# PCB_moved_parts_3.net
KiCad netlist of a schematic drawn in EAGLE
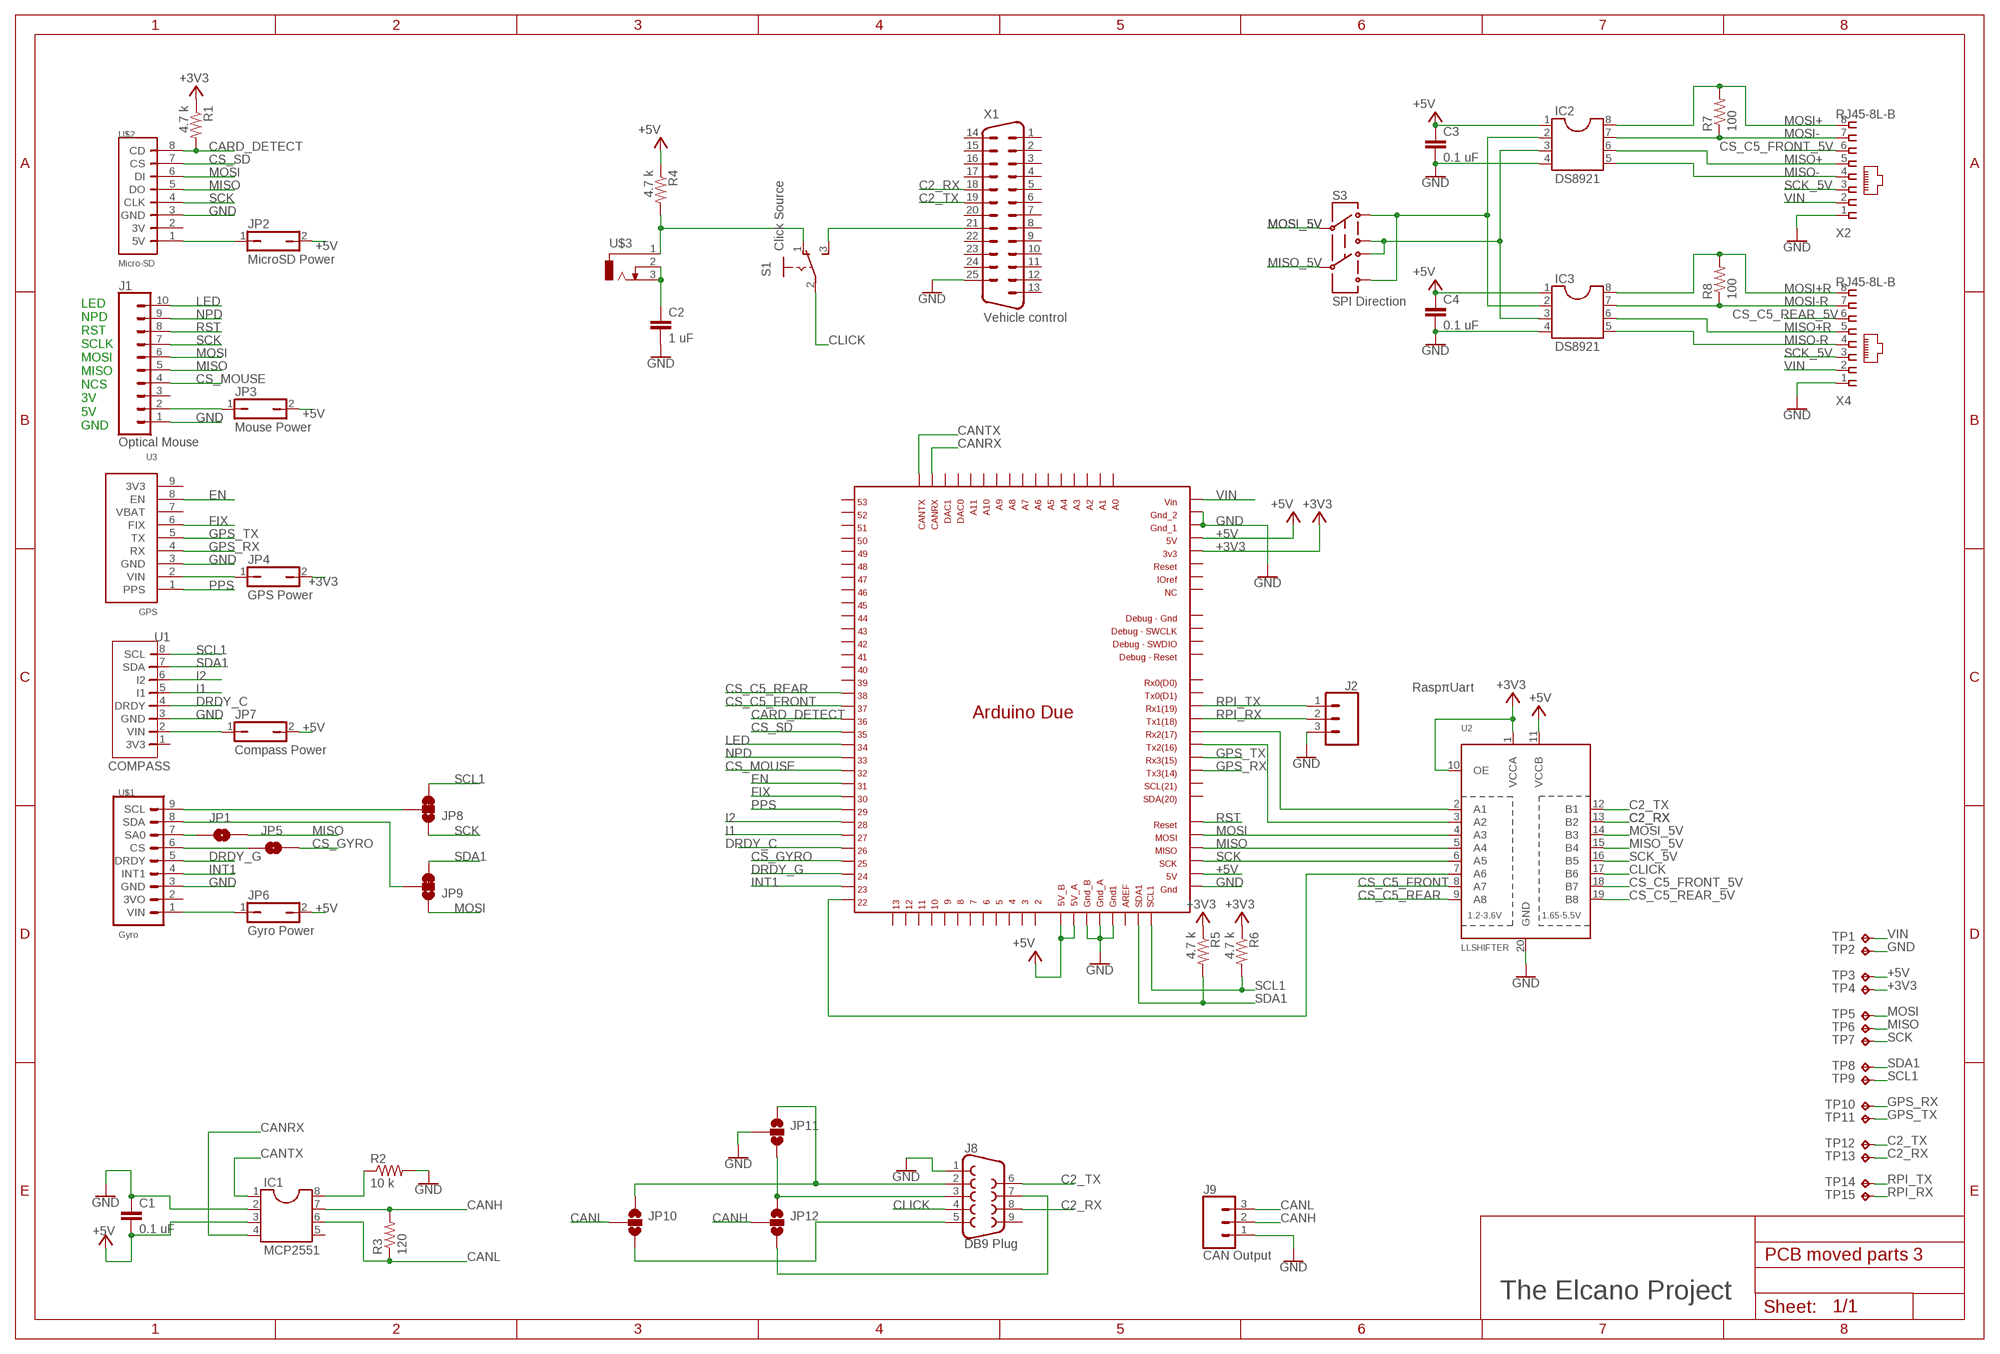
[diagram p0: schematic, sheet 1]

(export (version "E")
  (design (tool "Eeschema 10.0.6"))
  (components
    (comp (ref "C1")
      (value "0.1 uF")
      (footprint "eagle-import:C2.5-5")
      (libsource (lib "eagle-import") (part "C2.5/5"))
    )
    (comp (ref "C2")
      (value "1 uF")
      (footprint "eagle-import:C2.5-5")
      (libsource (lib "eagle-import") (part "C2.5/5"))
    )
    (comp (ref "C3")
      (value "0.1 uF")
      (footprint "eagle-import:C2.5-5")
      (libsource (lib "eagle-import") (part "C2.5/5"))
    )
    (comp (ref "C4")
      (value "0.1 uF")
      (footprint "eagle-import:C2.5-5")
      (libsource (lib "eagle-import") (part "C2.5/5"))
    )
    (comp (ref "IC1")
      (value "MCP2551")
      (footprint "eagle-import:DIL08")
      (libsource (lib "eagle-import") (part "DIL8"))
    )
    (comp (ref "IC2")
      (value "DS8921")
      (footprint "eagle-import:DIL08")
      (libsource (lib "eagle-import") (part "DIL8"))
    )
    (comp (ref "IC3")
      (value "DS8921")
      (footprint "eagle-import:DIL08")
      (libsource (lib "eagle-import") (part "DIL8"))
    )
    (comp (ref "J1")
      (value "Optical Mouse")
      (footprint "eagle-import:1X10")
      (libsource (lib "eagle-import") (part "CONN_10{dblquote}"))
    )
    (comp (ref "J2")
      (value "RaspπUart")
      (footprint "eagle-import:1X03")
      (libsource (lib "eagle-import") (part "CONN_02"))
    )
    (comp (ref "J8")
      (value "DB9 Plug")
      (footprint "eagle-import:DB9_MALE")
      (fields (field (name "SPICEPREFIX") "X"))
      (libsource (lib "eagle-import") (part "DB9MALE"))
    )
    (comp (ref "J9")
      (value "CAN Output")
      (footprint "eagle-import:SCREWTERMINAL-5MM-3")
      (libsource (lib "eagle-import") (part "CONN_03-SCREW-5MM"))
    )
    (comp (ref "JP1")
      (value "JUMPER-SMT_2_NO_SILK")
      (footprint "eagle-import:SMT-JUMPER_2_NO_SILK")
      (libsource (lib "eagle-import") (part "JUMPER-SMT_2_NO_SILK"))
    )
    (comp (ref "JP2")
      (value "MicroSD Power")
      (footprint "eagle-import:JP1")
      (libsource (lib "eagle-import") (part "JP1Q"))
    )
    (comp (ref "JP3")
      (value "Mouse Power")
      (footprint "eagle-import:JP1")
      (libsource (lib "eagle-import") (part "JP1Q"))
    )
    (comp (ref "JP4")
      (value "GPS Power")
      (footprint "eagle-import:JP1")
      (libsource (lib "eagle-import") (part "JP1Q"))
    )
    (comp (ref "JP5")
      (value "JUMPER-SMT_2_NO_SILK")
      (footprint "eagle-import:SMT-JUMPER_2_NO_SILK")
      (libsource (lib "eagle-import") (part "JUMPER-SMT_2_NO_SILK"))
    )
    (comp (ref "JP6")
      (value "Gyro Power")
      (footprint "eagle-import:JP1")
      (libsource (lib "eagle-import") (part "JP1Q"))
    )
    (comp (ref "JP7")
      (value "Compass Power")
      (footprint "eagle-import:JP1")
      (libsource (lib "eagle-import") (part "JP1Q"))
    )
    (comp (ref "JP8")
      (value "JUMPER-SMT_3_1-NC_TRACE_SILK")
      (footprint "eagle-import:SMT-JUMPER_3_1-NC_TRACE_SILK")
      (libsource (lib "eagle-import") (part "JUMPER-SMT_3_1-NC_TRACE_SILK"))
    )
    (comp (ref "JP9")
      (value "JUMPER-SMT_3_1-NC_TRACE_SILK")
      (footprint "eagle-import:SMT-JUMPER_3_1-NC_TRACE_SILK")
      (libsource (lib "eagle-import") (part "JUMPER-SMT_3_1-NC_TRACE_SILK"))
    )
    (comp (ref "JP10")
      (value "JUMPER-SMT_3_NO_SILK")
      (footprint "eagle-import:SMT-JUMPER_3_NO_SILK")
      (libsource (lib "eagle-import") (part "JUMPER-SMT_3_NO_SILK"))
    )
    (comp (ref "JP11")
      (value "JUMPER-SMT_3_NO_SILK")
      (footprint "eagle-import:SMT-JUMPER_3_NO_SILK")
      (libsource (lib "eagle-import") (part "JUMPER-SMT_3_NO_SILK"))
    )
    (comp (ref "JP12")
      (value "JUMPER-SMT_3_NO_SILK")
      (footprint "eagle-import:SMT-JUMPER_3_NO_SILK")
      (libsource (lib "eagle-import") (part "JUMPER-SMT_3_NO_SILK"))
    )
    (comp (ref "MCU2")
      (value "DUE(NORMAL)")
      (footprint "eagle-import:DUE(NORMAL)")
      (libsource (lib "eagle-import") (part "DUE(NORMAL)"))
    )
    (comp (ref "R1")
      (value "4.7 k")
      (footprint "eagle-import:0204_7")
      (libsource (lib "eagle-import") (part "resistor_348_R-US_0204/7"))
    )
    (comp (ref "R2")
      (value "10 k")
      (footprint "eagle-import:0204_7")
      (libsource (lib "eagle-import") (part "R-US_0204/7"))
    )
    (comp (ref "R3")
      (value "120")
      (footprint "eagle-import:0204_7")
      (libsource (lib "eagle-import") (part "R-US_0204/7"))
    )
    (comp (ref "R4")
      (value "4.7 k")
      (footprint "eagle-import:0204_7")
      (libsource (lib "eagle-import") (part "resistor_348_R-US_0204/7"))
    )
    (comp (ref "R5")
      (value "4.7 k")
      (footprint "eagle-import:0204_7")
      (libsource (lib "eagle-import") (part "resistor_348_R-US_0204/7"))
    )
    (comp (ref "R6")
      (value "4.7 k")
      (footprint "eagle-import:0204_7")
      (libsource (lib "eagle-import") (part "resistor_348_R-US_0204/7"))
    )
    (comp (ref "R7")
      (value "100")
      (footprint "eagle-import:0204_7")
      (libsource (lib "eagle-import") (part "R-US_0204/7"))
    )
    (comp (ref "R8")
      (value "100")
      (footprint "eagle-import:0204_7")
      (libsource (lib "eagle-import") (part "R-US_0204/7"))
    )
    (comp (ref "S1")
      (value "Click Source")
      (footprint "eagle-import:255SB")
      (libsource (lib "eagle-import") (part "255SB"))
    )
    (comp (ref "S3")
      (value "SPI Direction")
      (footprint "eagle-import:DPDT")
      (libsource (lib "eagle-import") (part "DPDT"))
    )
    (comp (ref "TP1")
      (value "TPPAD1-17")
      (footprint "eagle-import:P1-17")
      (libsource (lib "eagle-import") (part "TPPAD1-17"))
    )
    (comp (ref "TP2")
      (value "TPPAD1-17")
      (footprint "eagle-import:P1-17")
      (libsource (lib "eagle-import") (part "TPPAD1-17"))
    )
    (comp (ref "TP3")
      (value "TPPAD1-17")
      (footprint "eagle-import:P1-17")
      (libsource (lib "eagle-import") (part "TPPAD1-17"))
    )
    (comp (ref "TP4")
      (value "TPPAD1-17")
      (footprint "eagle-import:P1-17")
      (libsource (lib "eagle-import") (part "TPPAD1-17"))
    )
    (comp (ref "TP5")
      (value "TPPAD1-17")
      (footprint "eagle-import:P1-17")
      (libsource (lib "eagle-import") (part "TPPAD1-17"))
    )
    (comp (ref "TP6")
      (value "TPPAD1-17")
      (footprint "eagle-import:P1-17")
      (libsource (lib "eagle-import") (part "TPPAD1-17"))
    )
    (comp (ref "TP7")
      (value "TPPAD1-17")
      (footprint "eagle-import:P1-17")
      (libsource (lib "eagle-import") (part "TPPAD1-17"))
    )
    (comp (ref "TP8")
      (value "TPPAD1-17")
      (footprint "eagle-import:P1-17")
      (libsource (lib "eagle-import") (part "TPPAD1-17"))
    )
    (comp (ref "TP9")
      (value "TPPAD1-17")
      (footprint "eagle-import:P1-17")
      (libsource (lib "eagle-import") (part "TPPAD1-17"))
    )
    (comp (ref "TP10")
      (value "TPPAD1-17")
      (footprint "eagle-import:P1-17")
      (libsource (lib "eagle-import") (part "TPPAD1-17"))
    )
    (comp (ref "TP11")
      (value "TPPAD1-17")
      (footprint "eagle-import:P1-17")
      (libsource (lib "eagle-import") (part "TPPAD1-17"))
    )
    (comp (ref "TP12")
      (value "TPPAD1-17")
      (footprint "eagle-import:P1-17")
      (libsource (lib "eagle-import") (part "TPPAD1-17"))
    )
    (comp (ref "TP13")
      (value "TPPAD1-17")
      (footprint "eagle-import:P1-17")
      (libsource (lib "eagle-import") (part "TPPAD1-17"))
    )
    (comp (ref "TP14")
      (value "TPPAD1-17")
      (footprint "eagle-import:P1-17")
      (libsource (lib "eagle-import") (part "TPPAD1-17"))
    )
    (comp (ref "TP15")
      (value "TPPAD1-17")
      (footprint "eagle-import:P1-17")
      (libsource (lib "eagle-import") (part "TPPAD1-17"))
    )
    (comp (ref "U$1")
      (value "Gyro")
      (footprint "eagle-import:ELGYRO")
      (libsource (lib "eagle-import") (part "ELGYRO_L3GD20H"))
    )
    (comp (ref "U$2")
      (value "Micro-SD")
      (footprint "eagle-import:ELSDCARD")
      (libsource (lib "eagle-import") (part "MINI_SD"))
    )
    (comp (ref "U$3")
      (value "2.5MMJACK")
      (footprint "eagle-import:2.5MMJACK")
      (libsource (lib "eagle-import") (part "2.5MMJACK"))
    )
    (comp (ref "U1")
      (value "COMPASS")
      (footprint "eagle-import:ELCOMPASS")
      (libsource (lib "eagle-import") (part "ELCOMPASS"))
    )
    (comp (ref "U2")
      (value "LLSHIFTER")
      (footprint "eagle-import:ELSHIFTER")
      (libsource (lib "eagle-import") (part "ELSHIFTER"))
    )
    (comp (ref "U3")
      (value "GPS")
      (footprint "eagle-import:ELGPS")
      (libsource (lib "eagle-import") (part "ELGPS"))
    )
    (comp (ref "X1")
      (value "Vehicle control")
      (footprint "eagle-import:M25H")
      (libsource (lib "eagle-import") (part "M25H"))
    )
    (comp (ref "X2")
      (value "RJ45-8L-B")
      (footprint "eagle-import:RJ45-NO-SHIELD")
      (fields (field (name "MF") "TYCO ELECTRONICS"))
      (libsource (lib "eagle-import") (part "RJ45-8L-B"))
    )
    (comp (ref "X4")
      (value "RJ45-8L-B")
      (footprint "eagle-import:RJ45-NO-SHIELD")
      (fields (field (name "MF") "TYCO ELECTRONICS"))
      (libsource (lib "eagle-import") (part "RJ45-8L-B"))
    )
  )
  (nets
    (net (code "1") (name "+3V3") (class "Default")
      (node (ref "JP4") (pin "2") (pinfunction "2_2") (pintype "passive"))
      (node (ref "MCU2") (pin "3V3") (pinfunction "3V3_3V3") (pintype "bidirectional"))
      (node (ref "R1") (pin "1") (pinfunction "1_1") (pintype "passive"))
      (node (ref "R5") (pin "1") (pinfunction "1_1") (pintype "passive"))
      (node (ref "R6") (pin "1") (pinfunction "1_1") (pintype "passive"))
      (node (ref "TP4") (pin "TP") (pinfunction "TP_TP") (pintype "input"))
      (node (ref "U2") (pin "1") (pinfunction "VCCA_1") (pintype "power_in"))
      (node (ref "U2") (pin "10") (pinfunction "OE_10") (pintype "bidirectional"))
    )
    (net (code "2") (name "+5V") (class "Default")
      (node (ref "C1") (pin "2") (pinfunction "2_2") (pintype "passive"))
      (node (ref "C3") (pin "1") (pinfunction "1_1") (pintype "passive"))
      (node (ref "C4") (pin "1") (pinfunction "1_1") (pintype "passive"))
      (node (ref "IC1") (pin "3") (pinfunction "3_3") (pintype "passive"))
      (node (ref "IC2") (pin "1") (pinfunction "1_1") (pintype "passive"))
      (node (ref "IC3") (pin "1") (pinfunction "1_1") (pintype "passive"))
      (node (ref "JP2") (pin "2") (pinfunction "2_2") (pintype "passive"))
      (node (ref "JP3") (pin "2") (pinfunction "2_2") (pintype "passive"))
      (node (ref "JP6") (pin "2") (pinfunction "2_2") (pintype "passive"))
      (node (ref "JP7") (pin "2") (pinfunction "2_2") (pintype "passive"))
      (node (ref "MCU2") (pin "5V") (pinfunction "5V_5V") (pintype "bidirectional"))
      (node (ref "MCU2") (pin "5V_A") (pinfunction "5V_A_5V_A") (pintype "bidirectional"))
      (node (ref "MCU2") (pin "5V_B") (pinfunction "5V_B_5V_B") (pintype "bidirectional"))
      (node (ref "MCU2") (pin "GND_ICSP") (pinfunction "GND_ICSP_GND_ICSP") (pintype "bidirectional"))
      (node (ref "R4") (pin "1") (pinfunction "1_1") (pintype "passive"))
      (node (ref "TP3") (pin "TP") (pinfunction "TP_TP") (pintype "input"))
      (node (ref "U2") (pin "11") (pinfunction "VCCB_11") (pintype "power_in"))
    )
    (net (code "3") (name "/C2_RX") (class "Default")
      (node (ref "J8") (pin "8") (pinfunction "8_8") (pintype "passive"))
      (node (ref "TP13") (pin "TP") (pinfunction "TP_TP") (pintype "input"))
      (node (ref "U2") (pin "13") (pinfunction "B2_13") (pintype "bidirectional"))
      (node (ref "X1") (pin "18") (pinfunction "18_18") (pintype "passive"))
    )
    (net (code "4") (name "/C2_TX") (class "Default")
      (node (ref "J8") (pin "6") (pinfunction "6_6") (pintype "passive"))
      (node (ref "TP12") (pin "TP") (pinfunction "TP_TP") (pintype "input"))
      (node (ref "U2") (pin "12") (pinfunction "B1_12") (pintype "bidirectional"))
      (node (ref "X1") (pin "19") (pinfunction "19_19") (pintype "passive"))
    )
    (net (code "5") (name "/CANH") (class "Default")
      (node (ref "IC1") (pin "7") (pinfunction "7_7") (pintype "passive"))
      (node (ref "J9") (pin "2") (pinfunction "2_2") (pintype "passive"))
      (node (ref "JP12") (pin "2") (pinfunction "2_2") (pintype "passive"))
      (node (ref "R3") (pin "2") (pinfunction "2_2") (pintype "passive"))
    )
    (net (code "6") (name "/CANL") (class "Default")
      (node (ref "IC1") (pin "6") (pinfunction "6_6") (pintype "passive"))
      (node (ref "J9") (pin "3") (pinfunction "3_3") (pintype "passive"))
      (node (ref "JP10") (pin "2") (pinfunction "2_2") (pintype "passive"))
      (node (ref "R3") (pin "1") (pinfunction "1_1") (pintype "passive"))
    )
    (net (code "7") (name "/CANRX") (class "Default")
      (node (ref "IC1") (pin "4") (pinfunction "4_4") (pintype "passive"))
      (node (ref "MCU2") (pin "CANRX") (pinfunction "CANRX_CANRX") (pintype "bidirectional"))
    )
    (net (code "8") (name "/CANTX") (class "Default")
      (node (ref "IC1") (pin "1") (pinfunction "1_1") (pintype "passive"))
      (node (ref "MCU2") (pin "CANTX") (pinfunction "CANTX_CANTX") (pintype "bidirectional"))
    )
    (net (code "9") (name "/CARD_DETECT") (class "Default")
      (node (ref "MCU2") (pin "36") (pinfunction "36_36") (pintype "bidirectional"))
      (node (ref "R1") (pin "2") (pinfunction "2_2") (pintype "passive"))
      (node (ref "U$2") (pin "8") (pinfunction "CD_8") (pintype "bidirectional"))
    )
    (net (code "10") (name "/CLICK") (class "Default")
      (node (ref "J8") (pin "4") (pinfunction "4_4") (pintype "passive"))
      (node (ref "S1") (pin "2") (pinfunction "P_2") (pintype "passive"))
      (node (ref "U2") (pin "17") (pinfunction "B6_17") (pintype "bidirectional"))
    )
    (net (code "11") (name "/CS_C5_FRONT") (class "Default")
      (node (ref "MCU2") (pin "37") (pinfunction "37_37") (pintype "bidirectional"))
      (node (ref "U2") (pin "8") (pinfunction "A7_8") (pintype "bidirectional"))
    )
    (net (code "12") (name "/CS_C5_FRONT_5V") (class "Default")
      (node (ref "U2") (pin "18") (pinfunction "B7_18") (pintype "bidirectional"))
      (node (ref "X2") (pin "6") (pinfunction "6_6") (pintype "passive"))
    )
    (net (code "13") (name "/CS_C5_REAR") (class "Default")
      (node (ref "MCU2") (pin "38") (pinfunction "38_38") (pintype "bidirectional"))
      (node (ref "U2") (pin "9") (pinfunction "A8_9") (pintype "bidirectional"))
    )
    (net (code "14") (name "/CS_C5_REAR_5V") (class "Default")
      (node (ref "U2") (pin "19") (pinfunction "B8_19") (pintype "bidirectional"))
      (node (ref "X4") (pin "6") (pinfunction "6_6") (pintype "passive"))
    )
    (net (code "15") (name "/CS_GYRO") (class "Default")
      (node (ref "JP5") (pin "2") (pinfunction "2_2") (pintype "passive"))
      (node (ref "MCU2") (pin "25") (pinfunction "25_25") (pintype "bidirectional"))
    )
    (net (code "16") (name "/CS_MOUSE") (class "Default")
      (node (ref "J1") (pin "4") (pinfunction "4_4") (pintype "passive"))
      (node (ref "MCU2") (pin "32") (pinfunction "32_32") (pintype "bidirectional"))
    )
    (net (code "17") (name "/CS_SD") (class "Default")
      (node (ref "MCU2") (pin "35") (pinfunction "35_35") (pintype "bidirectional"))
      (node (ref "U$2") (pin "7") (pinfunction "CS_7") (pintype "bidirectional"))
    )
    (net (code "18") (name "/DRDY_C") (class "Default")
      (node (ref "MCU2") (pin "26") (pinfunction "26_26") (pintype "bidirectional"))
      (node (ref "U1") (pin "4") (pinfunction "DRDY_4") (pintype "bidirectional"))
    )
    (net (code "19") (name "/DRDY_G") (class "Default")
      (node (ref "MCU2") (pin "24") (pinfunction "24_24") (pintype "bidirectional"))
      (node (ref "U$1") (pin "5") (pinfunction "DRDY_5") (pintype "passive"))
    )
    (net (code "20") (name "/EN") (class "Default")
      (node (ref "MCU2") (pin "31") (pinfunction "31_31") (pintype "bidirectional"))
      (node (ref "U3") (pin "8") (pinfunction "EN_8") (pintype "bidirectional"))
    )
    (net (code "21") (name "/FIX") (class "Default")
      (node (ref "MCU2") (pin "30") (pinfunction "30_30") (pintype "bidirectional"))
      (node (ref "U3") (pin "6") (pinfunction "FIX_6") (pintype "bidirectional"))
    )
    (net (code "22") (name "/GPS_RX") (class "Default")
      (node (ref "MCU2") (pin "TX3") (pinfunction "TX3_TX3") (pintype "bidirectional"))
      (node (ref "TP10") (pin "TP") (pinfunction "TP_TP") (pintype "input"))
      (node (ref "U3") (pin "4") (pinfunction "RX_4") (pintype "input"))
    )
    (net (code "23") (name "/GPS_TX") (class "Default")
      (node (ref "MCU2") (pin "RX3") (pinfunction "RX3_RX3") (pintype "bidirectional"))
      (node (ref "TP11") (pin "TP") (pinfunction "TP_TP") (pintype "input"))
      (node (ref "U3") (pin "5") (pinfunction "TX_5") (pintype "output"))
    )
    (net (code "24") (name "/I1") (class "Default")
      (node (ref "MCU2") (pin "27") (pinfunction "27_27") (pintype "bidirectional"))
      (node (ref "U1") (pin "5") (pinfunction "I1_5") (pintype "bidirectional"))
    )
    (net (code "25") (name "/I2") (class "Default")
      (node (ref "MCU2") (pin "28") (pinfunction "28_28") (pintype "bidirectional"))
      (node (ref "U1") (pin "6") (pinfunction "I2_6") (pintype "bidirectional"))
    )
    (net (code "26") (name "/INT1") (class "Default")
      (node (ref "MCU2") (pin "23") (pinfunction "23_23") (pintype "bidirectional"))
      (node (ref "U$1") (pin "4") (pinfunction "INT1_4") (pintype "passive"))
    )
    (net (code "27") (name "/LED") (class "Default")
      (node (ref "J1") (pin "10") (pinfunction "10_10") (pintype "passive"))
      (node (ref "MCU2") (pin "34") (pinfunction "34_34") (pintype "bidirectional"))
    )
    (net (code "28") (name "/MISO") (class "Default")
      (node (ref "J1") (pin "5") (pinfunction "5_5") (pintype "passive"))
      (node (ref "JP1") (pin "2") (pinfunction "2_2") (pintype "passive"))
      (node (ref "MCU2") (pin "MISO_ICSP") (pinfunction "MISO_ICSP_MISO_ICSP") (pintype "bidirectional"))
      (node (ref "TP6") (pin "TP") (pinfunction "TP_TP") (pintype "input"))
      (node (ref "U$2") (pin "5") (pinfunction "DO_5") (pintype "bidirectional"))
      (node (ref "U2") (pin "5") (pinfunction "A4_5") (pintype "bidirectional"))
    )
    (net (code "29") (name "/MISO+") (class "Default")
      (node (ref "IC2") (pin "6") (pinfunction "6_6") (pintype "passive"))
      (node (ref "X2") (pin "5") (pinfunction "5_5") (pintype "passive"))
    )
    (net (code "30") (name "/MISO+R") (class "Default")
      (node (ref "IC3") (pin "6") (pinfunction "6_6") (pintype "passive"))
      (node (ref "X4") (pin "5") (pinfunction "5_5") (pintype "passive"))
    )
    (net (code "31") (name "/MISO-") (class "Default")
      (node (ref "IC2") (pin "5") (pinfunction "5_5") (pintype "passive"))
      (node (ref "X2") (pin "4") (pinfunction "4_4") (pintype "passive"))
    )
    (net (code "32") (name "/MISO-R") (class "Default")
      (node (ref "IC3") (pin "5") (pinfunction "5_5") (pintype "passive"))
      (node (ref "X4") (pin "4") (pinfunction "4_4") (pintype "passive"))
    )
    (net (code "33") (name "/MISO_5V") (class "Default")
      (node (ref "S3") (pin "5") (pinfunction "5_5") (pintype "bidirectional"))
      (node (ref "U2") (pin "15") (pinfunction "B4_15") (pintype "bidirectional"))
    )
    (net (code "34") (name "/MOSI") (class "Default")
      (node (ref "J1") (pin "6") (pinfunction "6_6") (pintype "passive"))
      (node (ref "JP9") (pin "1") (pinfunction "1_1") (pintype "passive"))
      (node (ref "MCU2") (pin "MOSI_ICSP") (pinfunction "MOSI_ICSP_MOSI_ICSP") (pintype "bidirectional"))
      (node (ref "TP5") (pin "TP") (pinfunction "TP_TP") (pintype "input"))
      (node (ref "U$2") (pin "6") (pinfunction "DI_6") (pintype "bidirectional"))
      (node (ref "U2") (pin "4") (pinfunction "A3_4") (pintype "bidirectional"))
    )
    (net (code "35") (name "/MOSI+") (class "Default")
      (node (ref "IC2") (pin "8") (pinfunction "8_8") (pintype "passive"))
      (node (ref "R7") (pin "2") (pinfunction "2_2") (pintype "passive"))
      (node (ref "X2") (pin "8") (pinfunction "8_8") (pintype "passive"))
    )
    (net (code "36") (name "/MOSI+R") (class "Default")
      (node (ref "IC3") (pin "8") (pinfunction "8_8") (pintype "passive"))
      (node (ref "R8") (pin "2") (pinfunction "2_2") (pintype "passive"))
      (node (ref "X4") (pin "8") (pinfunction "8_8") (pintype "passive"))
    )
    (net (code "37") (name "/MOSI-") (class "Default")
      (node (ref "IC2") (pin "7") (pinfunction "7_7") (pintype "passive"))
      (node (ref "R7") (pin "1") (pinfunction "1_1") (pintype "passive"))
      (node (ref "X2") (pin "7") (pinfunction "7_7") (pintype "passive"))
    )
    (net (code "38") (name "/MOSI-R") (class "Default")
      (node (ref "IC3") (pin "7") (pinfunction "7_7") (pintype "passive"))
      (node (ref "R8") (pin "1") (pinfunction "1_1") (pintype "passive"))
      (node (ref "X4") (pin "7") (pinfunction "7_7") (pintype "passive"))
    )
    (net (code "39") (name "/MOSI_5V") (class "Default")
      (node (ref "S3") (pin "2") (pinfunction "2_2") (pintype "bidirectional"))
      (node (ref "U2") (pin "14") (pinfunction "B3_14") (pintype "bidirectional"))
    )
    (net (code "40") (name "/NPD") (class "Default")
      (node (ref "J1") (pin "9") (pinfunction "9_9") (pintype "passive"))
      (node (ref "MCU2") (pin "33") (pinfunction "33_33") (pintype "bidirectional"))
    )
    (net (code "41") (name "/PPS") (class "Default")
      (node (ref "MCU2") (pin "29") (pinfunction "29_29") (pintype "bidirectional"))
      (node (ref "U3") (pin "1") (pinfunction "PPS_1") (pintype "bidirectional"))
    )
    (net (code "42") (name "/RPI_RX") (class "Default")
      (node (ref "J2") (pin "2") (pinfunction "1_2") (pintype "passive"))
      (node (ref "MCU2") (pin "TX1") (pinfunction "TX1_TX1") (pintype "bidirectional"))
      (node (ref "TP15") (pin "TP") (pinfunction "TP_TP") (pintype "input"))
    )
    (net (code "43") (name "/RPI_TX") (class "Default")
      (node (ref "J2") (pin "1") (pinfunction "2_1") (pintype "passive"))
      (node (ref "MCU2") (pin "RX1") (pinfunction "RX1_RX1") (pintype "bidirectional"))
      (node (ref "TP14") (pin "TP") (pinfunction "TP_TP") (pintype "input"))
    )
    (net (code "44") (name "/RST") (class "Default")
      (node (ref "J1") (pin "8") (pinfunction "8_8") (pintype "passive"))
      (node (ref "MCU2") (pin "RESET_ICSP") (pinfunction "RESET_ICSP_RESET_ICSP") (pintype "bidirectional"))
    )
    (net (code "45") (name "/SCK") (class "Default")
      (node (ref "J1") (pin "7") (pinfunction "7_7") (pintype "passive"))
      (node (ref "JP8") (pin "1") (pinfunction "1_1") (pintype "passive"))
      (node (ref "MCU2") (pin "SCK_ICSP") (pinfunction "SCK_ICSP_SCK_ICSP") (pintype "bidirectional"))
      (node (ref "TP7") (pin "TP") (pinfunction "TP_TP") (pintype "input"))
      (node (ref "U$2") (pin "4") (pinfunction "CLK_4") (pintype "bidirectional"))
      (node (ref "U2") (pin "6") (pinfunction "A5_6") (pintype "bidirectional"))
    )
    (net (code "46") (name "/SCK_5V") (class "Default")
      (node (ref "U2") (pin "16") (pinfunction "B5_16") (pintype "bidirectional"))
      (node (ref "X2") (pin "3") (pinfunction "3_3") (pintype "passive"))
      (node (ref "X4") (pin "3") (pinfunction "3_3") (pintype "passive"))
    )
    (net (code "47") (name "/SCL1") (class "Default")
      (node (ref "JP8") (pin "3") (pinfunction "3_3") (pintype "passive"))
      (node (ref "MCU2") (pin "SCL1") (pinfunction "SCL1_SCL1") (pintype "bidirectional"))
      (node (ref "R6") (pin "2") (pinfunction "2_2") (pintype "passive"))
      (node (ref "TP9") (pin "TP") (pinfunction "TP_TP") (pintype "input"))
      (node (ref "U1") (pin "8") (pinfunction "SCL_8") (pintype "bidirectional"))
    )
    (net (code "48") (name "/SDA1") (class "Default")
      (node (ref "JP9") (pin "3") (pinfunction "3_3") (pintype "passive"))
      (node (ref "MCU2") (pin "SDA1") (pinfunction "SDA1_SDA1") (pintype "bidirectional"))
      (node (ref "R5") (pin "2") (pinfunction "2_2") (pintype "passive"))
      (node (ref "TP8") (pin "TP") (pinfunction "TP_TP") (pintype "input"))
      (node (ref "U1") (pin "7") (pinfunction "SDA_7") (pintype "bidirectional"))
    )
    (net (code "49") (name "/VIN") (class "Default")
      (node (ref "MCU2") (pin "VIN") (pinfunction "VIN_VIN") (pintype "bidirectional"))
      (node (ref "TP1") (pin "TP") (pinfunction "TP_TP") (pintype "input"))
      (node (ref "X2") (pin "2") (pinfunction "2_2") (pintype "passive"))
      (node (ref "X4") (pin "2") (pinfunction "2_2") (pintype "passive"))
    )
    (net (code "50") (name "GND") (class "Default")
      (node (ref "C1") (pin "1") (pinfunction "1_1") (pintype "passive"))
      (node (ref "C2") (pin "2") (pinfunction "2_2") (pintype "passive"))
      (node (ref "C3") (pin "2") (pinfunction "2_2") (pintype "passive"))
      (node (ref "C4") (pin "2") (pinfunction "2_2") (pintype "passive"))
      (node (ref "IC1") (pin "2") (pinfunction "2_2") (pintype "passive"))
      (node (ref "IC2") (pin "4") (pinfunction "4_4") (pintype "passive"))
      (node (ref "IC3") (pin "4") (pinfunction "4_4") (pintype "passive"))
      (node (ref "J1") (pin "1") (pinfunction "1_1") (pintype "passive"))
      (node (ref "J2") (pin "3") (pinfunction "3_3") (pintype "passive"))
      (node (ref "J8") (pin "1") (pinfunction "1_1") (pintype "passive"))
      (node (ref "J9") (pin "1") (pinfunction "1_1") (pintype "passive"))
      (node (ref "JP11") (pin "2") (pinfunction "2_2") (pintype "passive"))
      (node (ref "MCU2") (pin "5V_ICSP") (pinfunction "5V_ICSP_5V_ICSP") (pintype "bidirectional"))
      (node (ref "MCU2") (pin "GND1") (pinfunction "GND1_GND1") (pintype "bidirectional"))
      (node (ref "MCU2") (pin "GND_1") (pinfunction "GND_1_GND_1") (pintype "bidirectional"))
      (node (ref "MCU2") (pin "GND_2") (pinfunction "GND_2_GND_2") (pintype "bidirectional"))
      (node (ref "MCU2") (pin "GND_A") (pinfunction "GND_A_GND_A") (pintype "bidirectional"))
      (node (ref "MCU2") (pin "GND_B") (pinfunction "GND_B_GND_B") (pintype "bidirectional"))
      (node (ref "R2") (pin "2") (pinfunction "2_2") (pintype "passive"))
      (node (ref "TP2") (pin "TP") (pinfunction "TP_TP") (pintype "input"))
      (node (ref "U$1") (pin "3") (pinfunction "GND_3") (pintype "passive"))
      (node (ref "U$2") (pin "3") (pinfunction "GND_3") (pintype "bidirectional"))
      (node (ref "U1") (pin "3") (pinfunction "GND_3") (pintype "power_in"))
      (node (ref "U2") (pin "20") (pinfunction "GND_20") (pintype "power_in"))
      (node (ref "U3") (pin "3") (pinfunction "GND_3") (pintype "power_in"))
      (node (ref "X1") (pin "25") (pinfunction "25_25") (pintype "passive"))
      (node (ref "X2") (pin "1") (pinfunction "1_1") (pintype "passive"))
      (node (ref "X4") (pin "1") (pinfunction "1_1") (pintype "passive"))
    )
    (net (code "51") (name "Net-(C2-Pad1)") (class "Default")
      (node (ref "C2") (pin "1") (pinfunction "1_1") (pintype "passive"))
      (node (ref "U$3") (pin "2") (pinfunction "2_2") (pintype "passive"))
      (node (ref "U$3") (pin "3") (pinfunction "3_3") (pintype "passive"))
    )
    (net (code "52") (name "Net-(IC1-Pad8)") (class "Default")
      (node (ref "IC1") (pin "8") (pinfunction "8_8") (pintype "passive"))
      (node (ref "R2") (pin "1") (pinfunction "1_1") (pintype "passive"))
    )
    (net (code "53") (name "Net-(IC2-Pad2)") (class "Default")
      (node (ref "IC2") (pin "2") (pinfunction "2_2") (pintype "passive"))
      (node (ref "IC3") (pin "2") (pinfunction "2_2") (pintype "passive"))
      (node (ref "S3") (pin "1") (pinfunction "1_1") (pintype "bidirectional"))
      (node (ref "S3") (pin "6") (pinfunction "6_6") (pintype "bidirectional"))
    )
    (net (code "54") (name "Net-(IC2-Pad3)") (class "Default")
      (node (ref "IC2") (pin "3") (pinfunction "3_3") (pintype "passive"))
      (node (ref "IC3") (pin "3") (pinfunction "3_3") (pintype "passive"))
      (node (ref "S3") (pin "3") (pinfunction "3_3") (pintype "bidirectional"))
      (node (ref "S3") (pin "4") (pinfunction "4_4") (pintype "bidirectional"))
    )
    (net (code "55") (name "Net-(J1-Pad2)") (class "Default")
      (node (ref "J1") (pin "2") (pinfunction "2_2") (pintype "passive"))
      (node (ref "JP3") (pin "1") (pinfunction "1_1") (pintype "passive"))
    )
    (net (code "56") (name "Net-(J8-Pad2)") (class "Default")
      (node (ref "J8") (pin "2") (pinfunction "2_2") (pintype "passive"))
      (node (ref "JP10") (pin "1") (pinfunction "1_1") (pintype "passive"))
      (node (ref "JP11") (pin "1") (pinfunction "1_1") (pintype "passive"))
    )
    (net (code "57") (name "Net-(J8-Pad3)") (class "Default")
      (node (ref "J8") (pin "3") (pinfunction "3_3") (pintype "passive"))
      (node (ref "JP11") (pin "3") (pinfunction "3_3") (pintype "passive"))
      (node (ref "JP12") (pin "1") (pinfunction "1_1") (pintype "passive"))
    )
    (net (code "58") (name "Net-(J8-Pad5)") (class "Default")
      (node (ref "J8") (pin "5") (pinfunction "5_5") (pintype "passive"))
      (node (ref "JP10") (pin "3") (pinfunction "3_3") (pintype "passive"))
    )
    (net (code "59") (name "Net-(J8-Pad7)") (class "Default")
      (node (ref "J8") (pin "7") (pinfunction "7_7") (pintype "passive"))
      (node (ref "JP12") (pin "3") (pinfunction "3_3") (pintype "passive"))
    )
    (net (code "60") (name "Net-(S1-O)") (class "Default")
      (node (ref "R4") (pin "2") (pinfunction "2_2") (pintype "passive"))
      (node (ref "S1") (pin "1") (pinfunction "O_1") (pintype "passive"))
      (node (ref "U$3") (pin "1") (pinfunction "1_1") (pintype "passive"))
    )
    (net (code "61") (name "Net-(S1-S)") (class "Default")
      (node (ref "S1") (pin "3") (pinfunction "S_3") (pintype "passive"))
      (node (ref "X1") (pin "21") (pinfunction "21_21") (pintype "passive"))
    )
    (net (code "62") (name "Net-(U$1-CS)") (class "Default")
      (node (ref "JP5") (pin "1") (pinfunction "1_1") (pintype "passive"))
      (node (ref "U$1") (pin "6") (pinfunction "CS_6") (pintype "passive"))
    )
    (net (code "63") (name "Net-(U$1-SA0)") (class "Default")
      (node (ref "JP1") (pin "1") (pinfunction "1_1") (pintype "passive"))
      (node (ref "U$1") (pin "7") (pinfunction "SA0_7") (pintype "passive"))
    )
    (net (code "64") (name "Net-(U$1-SCL)") (class "Default")
      (node (ref "JP8") (pin "2") (pinfunction "2_2") (pintype "passive"))
      (node (ref "U$1") (pin "9") (pinfunction "SCL_9") (pintype "passive"))
    )
    (net (code "65") (name "Net-(U$1-SDA)") (class "Default")
      (node (ref "JP9") (pin "2") (pinfunction "2_2") (pintype "passive"))
      (node (ref "U$1") (pin "8") (pinfunction "SDA_8") (pintype "passive"))
    )
    (net (code "66") (name "Net-(U$1-VIN)") (class "Default")
      (node (ref "JP6") (pin "1") (pinfunction "1_1") (pintype "passive"))
      (node (ref "U$1") (pin "1") (pinfunction "VIN_1") (pintype "passive"))
    )
    (net (code "67") (name "Net-(U$2-5V)") (class "Default")
      (node (ref "JP2") (pin "1") (pinfunction "1_1") (pintype "passive"))
      (node (ref "U$2") (pin "1") (pinfunction "5V_1") (pintype "bidirectional"))
    )
    (net (code "68") (name "Net-(U1-VIN)") (class "Default")
      (node (ref "JP7") (pin "1") (pinfunction "1_1") (pintype "passive"))
      (node (ref "U1") (pin "2") (pinfunction "VIN_2") (pintype "power_in"))
    )
    (net (code "69") (name "Net-(U2-A1)") (class "Default")
      (node (ref "MCU2") (pin "RX2") (pinfunction "RX2_RX2") (pintype "bidirectional"))
      (node (ref "U2") (pin "2") (pinfunction "A1_2") (pintype "bidirectional"))
    )
    (net (code "70") (name "Net-(U2-A2)") (class "Default")
      (node (ref "MCU2") (pin "TX2") (pinfunction "TX2_TX2") (pintype "bidirectional"))
      (node (ref "U2") (pin "3") (pinfunction "A2_3") (pintype "bidirectional"))
    )
    (net (code "71") (name "Net-(U2-A6)") (class "Default")
      (node (ref "MCU2") (pin "22") (pinfunction "22_22") (pintype "bidirectional"))
      (node (ref "U2") (pin "7") (pinfunction "A6_7") (pintype "bidirectional"))
    )
    (net (code "72") (name "Net-(U3-VIN)") (class "Default")
      (node (ref "JP4") (pin "1") (pinfunction "1_1") (pintype "passive"))
      (node (ref "U3") (pin "2") (pinfunction "VIN_2") (pintype "power_in"))
    )
    (net (code "73") (name "unconnected-(IC1-Pad5)") (class "Default")
      (node (ref "IC1") (pin "5") (pinfunction "5_5") (pintype "passive"))
    )
    (net (code "74") (name "unconnected-(J1-Pad3)") (class "Default")
      (node (ref "J1") (pin "3") (pinfunction "3_3") (pintype "passive"))
    )
    (net (code "75") (name "unconnected-(J8-Pad9)") (class "Default")
      (node (ref "J8") (pin "9") (pinfunction "9_9") (pintype "passive"))
    )
    (net (code "76") (name "unconnected-(MCU2-Pad2)") (class "Default")
      (node (ref "MCU2") (pin "2") (pinfunction "2_2") (pintype "bidirectional"))
    )
    (net (code "77") (name "unconnected-(MCU2-Pad3)") (class "Default")
      (node (ref "MCU2") (pin "3") (pinfunction "3_3") (pintype "bidirectional"))
    )
    (net (code "78") (name "unconnected-(MCU2-Pad4)") (class "Default")
      (node (ref "MCU2") (pin "4") (pinfunction "4_4") (pintype "bidirectional"))
    )
    (net (code "79") (name "unconnected-(MCU2-Pad5)") (class "Default")
      (node (ref "MCU2") (pin "5") (pinfunction "5_5") (pintype "bidirectional"))
    )
    (net (code "80") (name "unconnected-(MCU2-Pad6)") (class "Default")
      (node (ref "MCU2") (pin "6") (pinfunction "6_6") (pintype "bidirectional"))
    )
    (net (code "81") (name "unconnected-(MCU2-Pad7)") (class "Default")
      (node (ref "MCU2") (pin "7") (pinfunction "7_7") (pintype "bidirectional"))
    )
    (net (code "82") (name "unconnected-(MCU2-Pad8)") (class "Default")
      (node (ref "MCU2") (pin "8") (pinfunction "8_8") (pintype "bidirectional"))
    )
    (net (code "83") (name "unconnected-(MCU2-Pad9)") (class "Default")
      (node (ref "MCU2") (pin "9") (pinfunction "9_9") (pintype "bidirectional"))
    )
    (net (code "84") (name "unconnected-(MCU2-Pad10)") (class "Default")
      (node (ref "MCU2") (pin "10") (pinfunction "10_10") (pintype "bidirectional"))
    )
    (net (code "85") (name "unconnected-(MCU2-Pad11)") (class "Default")
      (node (ref "MCU2") (pin "11") (pinfunction "11_11") (pintype "bidirectional"))
    )
    (net (code "86") (name "unconnected-(MCU2-Pad12)") (class "Default")
      (node (ref "MCU2") (pin "12") (pinfunction "12_12") (pintype "bidirectional"))
    )
    (net (code "87") (name "unconnected-(MCU2-Pad13)") (class "Default")
      (node (ref "MCU2") (pin "13") (pinfunction "13_13") (pintype "bidirectional"))
    )
    (net (code "88") (name "unconnected-(MCU2-Pad39)") (class "Default")
      (node (ref "MCU2") (pin "39") (pinfunction "39_39") (pintype "bidirectional"))
    )
    (net (code "89") (name "unconnected-(MCU2-Pad40)") (class "Default")
      (node (ref "MCU2") (pin "40") (pinfunction "40_40") (pintype "bidirectional"))
    )
    (net (code "90") (name "unconnected-(MCU2-Pad41)") (class "Default")
      (node (ref "MCU2") (pin "41") (pinfunction "41_41") (pintype "bidirectional"))
    )
    (net (code "91") (name "unconnected-(MCU2-Pad42)") (class "Default")
      (node (ref "MCU2") (pin "42") (pinfunction "42_42") (pintype "bidirectional"))
    )
    (net (code "92") (name "unconnected-(MCU2-Pad43)") (class "Default")
      (node (ref "MCU2") (pin "43") (pinfunction "43_43") (pintype "bidirectional"))
    )
    (net (code "93") (name "unconnected-(MCU2-Pad44)") (class "Default")
      (node (ref "MCU2") (pin "44") (pinfunction "44_44") (pintype "bidirectional"))
    )
    (net (code "94") (name "unconnected-(MCU2-Pad45)") (class "Default")
      (node (ref "MCU2") (pin "45") (pinfunction "45_45") (pintype "bidirectional"))
    )
    (net (code "95") (name "unconnected-(MCU2-Pad46)") (class "Default")
      (node (ref "MCU2") (pin "46") (pinfunction "46_46") (pintype "bidirectional"))
    )
    (net (code "96") (name "unconnected-(MCU2-Pad47)") (class "Default")
      (node (ref "MCU2") (pin "47") (pinfunction "47_47") (pintype "bidirectional"))
    )
    (net (code "97") (name "unconnected-(MCU2-Pad48)") (class "Default")
      (node (ref "MCU2") (pin "48") (pinfunction "48_48") (pintype "bidirectional"))
    )
    (net (code "98") (name "unconnected-(MCU2-Pad49)") (class "Default")
      (node (ref "MCU2") (pin "49") (pinfunction "49_49") (pintype "bidirectional"))
    )
    (net (code "99") (name "unconnected-(MCU2-Pad50)") (class "Default")
      (node (ref "MCU2") (pin "50") (pinfunction "50_50") (pintype "bidirectional"))
    )
    (net (code "100") (name "unconnected-(MCU2-Pad51)") (class "Default")
      (node (ref "MCU2") (pin "51") (pinfunction "51_51") (pintype "bidirectional"))
    )
    (net (code "101") (name "unconnected-(MCU2-Pad52)") (class "Default")
      (node (ref "MCU2") (pin "52") (pinfunction "52_52") (pintype "bidirectional"))
    )
    (net (code "102") (name "unconnected-(MCU2-Pad53)") (class "Default")
      (node (ref "MCU2") (pin "53") (pinfunction "53_53") (pintype "bidirectional"))
    )
    (net (code "103") (name "unconnected-(MCU2-PadA0)") (class "Default")
      (node (ref "MCU2") (pin "A0") (pinfunction "A0_A0") (pintype "bidirectional"))
    )
    (net (code "104") (name "unconnected-(MCU2-PadA1)") (class "Default")
      (node (ref "MCU2") (pin "A1") (pinfunction "A1_A1") (pintype "bidirectional"))
    )
    (net (code "105") (name "unconnected-(MCU2-PadA2)") (class "Default")
      (node (ref "MCU2") (pin "A2") (pinfunction "A2_A2") (pintype "bidirectional"))
    )
    (net (code "106") (name "unconnected-(MCU2-PadA3)") (class "Default")
      (node (ref "MCU2") (pin "A3") (pinfunction "A3_A3") (pintype "bidirectional"))
    )
    (net (code "107") (name "unconnected-(MCU2-PadA4)") (class "Default")
      (node (ref "MCU2") (pin "A4") (pinfunction "A4_A4") (pintype "bidirectional"))
    )
    (net (code "108") (name "unconnected-(MCU2-PadA5)") (class "Default")
      (node (ref "MCU2") (pin "A5") (pinfunction "A5_A5") (pintype "bidirectional"))
    )
    (net (code "109") (name "unconnected-(MCU2-PadA6)") (class "Default")
      (node (ref "MCU2") (pin "A6") (pinfunction "A6_A6") (pintype "bidirectional"))
    )
    (net (code "110") (name "unconnected-(MCU2-PadA7)") (class "Default")
      (node (ref "MCU2") (pin "A7") (pinfunction "A7_A7") (pintype "bidirectional"))
    )
    (net (code "111") (name "unconnected-(MCU2-PadA8)") (class "Default")
      (node (ref "MCU2") (pin "A8") (pinfunction "A8_A8") (pintype "bidirectional"))
    )
    (net (code "112") (name "unconnected-(MCU2-PadA9)") (class "Default")
      (node (ref "MCU2") (pin "A9") (pinfunction "A9_A9") (pintype "bidirectional"))
    )
    (net (code "113") (name "unconnected-(MCU2-PadA10)") (class "Default")
      (node (ref "MCU2") (pin "A10") (pinfunction "A10_A10") (pintype "bidirectional"))
    )
    (net (code "114") (name "unconnected-(MCU2-PadA11)") (class "Default")
      (node (ref "MCU2") (pin "A11") (pinfunction "A11_A11") (pintype "bidirectional"))
    )
    (net (code "115") (name "unconnected-(MCU2-PadAREF)") (class "Default")
      (node (ref "MCU2") (pin "AREF") (pinfunction "AREF_AREF") (pintype "bidirectional"))
    )
    (net (code "116") (name "unconnected-(MCU2-PadDAC0)") (class "Default")
      (node (ref "MCU2") (pin "DAC0") (pinfunction "DAC0_DAC0") (pintype "bidirectional"))
    )
    (net (code "117") (name "unconnected-(MCU2-PadDAC1)") (class "Default")
      (node (ref "MCU2") (pin "DAC1") (pinfunction "DAC1_DAC1") (pintype "bidirectional"))
    )
    (net (code "118") (name "unconnected-(MCU2-PadGND_DEBUG)") (class "Default")
      (node (ref "MCU2") (pin "GND_DEBUG") (pinfunction "GND_DEBUG_GND_DEBUG") (pintype "bidirectional"))
    )
    (net (code "119") (name "unconnected-(MCU2-PadIOREF)") (class "Default")
      (node (ref "MCU2") (pin "IOREF") (pinfunction "IOREF_IOREF") (pintype "bidirectional"))
    )
    (net (code "120") (name "unconnected-(MCU2-PadNC)") (class "Default")
      (node (ref "MCU2") (pin "NC") (pinfunction "NC_NC") (pintype "bidirectional"))
    )
    (net (code "121") (name "unconnected-(MCU2-PadRESET)") (class "Default")
      (node (ref "MCU2") (pin "RESET") (pinfunction "RESET_RESET") (pintype "bidirectional"))
    )
    (net (code "122") (name "unconnected-(MCU2-PadRESET_DEBUG)") (class "Default")
      (node (ref "MCU2") (pin "RESET_DEBUG") (pinfunction "RESET_DEBUG_RESET_DEBUG") (pintype "bidirectional"))
    )
    (net (code "123") (name "unconnected-(MCU2-PadRX0)") (class "Default")
      (node (ref "MCU2") (pin "RX0") (pinfunction "RX0_RX0") (pintype "bidirectional"))
    )
    (net (code "124") (name "unconnected-(MCU2-PadSCL)") (class "Default")
      (node (ref "MCU2") (pin "SCL") (pinfunction "SCL_SCL") (pintype "bidirectional"))
    )
    (net (code "125") (name "unconnected-(MCU2-PadSDA)") (class "Default")
      (node (ref "MCU2") (pin "SDA") (pinfunction "SDA_SDA") (pintype "bidirectional"))
    )
    (net (code "126") (name "unconnected-(MCU2-PadSWCLK_DEBUG)") (class "Default")
      (node (ref "MCU2") (pin "SWCLK_DEBUG") (pinfunction "SWCLK_DEBUG_SWCLK_DEBUG") (pintype "bidirectional"))
    )
    (net (code "127") (name "unconnected-(MCU2-PadSWDIO_DEBUG)") (class "Default")
      (node (ref "MCU2") (pin "SWDIO_DEBUG") (pinfunction "SWDIO_DEBUG_SWDIO_DEBUG") (pintype "bidirectional"))
    )
    (net (code "128") (name "unconnected-(MCU2-PadTX0)") (class "Default")
      (node (ref "MCU2") (pin "TX0") (pinfunction "TX0_TX0") (pintype "bidirectional"))
    )
    (net (code "129") (name "unconnected-(U$1-3VO-Pad2)") (class "Default")
      (node (ref "U$1") (pin "2") (pinfunction "3VO_2") (pintype "passive"))
    )
    (net (code "130") (name "unconnected-(U$2-3V-Pad2)") (class "Default")
      (node (ref "U$2") (pin "2") (pinfunction "3V_2") (pintype "bidirectional"))
    )
    (net (code "131") (name "unconnected-(U1-3V3-Pad1)") (class "Default")
      (node (ref "U1") (pin "1") (pinfunction "3V3_1") (pintype "no_connect"))
    )
    (net (code "132") (name "unconnected-(U3-3V3-Pad9)") (class "Default")
      (node (ref "U3") (pin "9") (pinfunction "3V3_9") (pintype "no_connect"))
    )
    (net (code "133") (name "unconnected-(U3-VBAT-Pad7)") (class "Default")
      (node (ref "U3") (pin "7") (pinfunction "VBAT_7") (pintype "no_connect"))
    )
    (net (code "134") (name "unconnected-(X1-Pad1)") (class "Default")
      (node (ref "X1") (pin "1") (pinfunction "1_1") (pintype "passive"))
    )
    (net (code "135") (name "unconnected-(X1-Pad2)") (class "Default")
      (node (ref "X1") (pin "2") (pinfunction "2_2") (pintype "passive"))
    )
    (net (code "136") (name "unconnected-(X1-Pad3)") (class "Default")
      (node (ref "X1") (pin "3") (pinfunction "3_3") (pintype "passive"))
    )
    (net (code "137") (name "unconnected-(X1-Pad4)") (class "Default")
      (node (ref "X1") (pin "4") (pinfunction "4_4") (pintype "passive"))
    )
    (net (code "138") (name "unconnected-(X1-Pad5)") (class "Default")
      (node (ref "X1") (pin "5") (pinfunction "5_5") (pintype "passive"))
    )
    (net (code "139") (name "unconnected-(X1-Pad6)") (class "Default")
      (node (ref "X1") (pin "6") (pinfunction "6_6") (pintype "passive"))
    )
    (net (code "140") (name "unconnected-(X1-Pad7)") (class "Default")
      (node (ref "X1") (pin "7") (pinfunction "7_7") (pintype "passive"))
    )
    (net (code "141") (name "unconnected-(X1-Pad8)") (class "Default")
      (node (ref "X1") (pin "8") (pinfunction "8_8") (pintype "passive"))
    )
    (net (code "142") (name "unconnected-(X1-Pad9)") (class "Default")
      (node (ref "X1") (pin "9") (pinfunction "9_9") (pintype "passive"))
    )
    (net (code "143") (name "unconnected-(X1-Pad10)") (class "Default")
      (node (ref "X1") (pin "10") (pinfunction "10_10") (pintype "passive"))
    )
    (net (code "144") (name "unconnected-(X1-Pad11)") (class "Default")
      (node (ref "X1") (pin "11") (pinfunction "11_11") (pintype "passive"))
    )
    (net (code "145") (name "unconnected-(X1-Pad12)") (class "Default")
      (node (ref "X1") (pin "12") (pinfunction "12_12") (pintype "passive"))
    )
    (net (code "146") (name "unconnected-(X1-Pad13)") (class "Default")
      (node (ref "X1") (pin "13") (pinfunction "13_13") (pintype "passive"))
    )
    (net (code "147") (name "unconnected-(X1-Pad14)") (class "Default")
      (node (ref "X1") (pin "14") (pinfunction "14_14") (pintype "passive"))
    )
    (net (code "148") (name "unconnected-(X1-Pad15)") (class "Default")
      (node (ref "X1") (pin "15") (pinfunction "15_15") (pintype "passive"))
    )
    (net (code "149") (name "unconnected-(X1-Pad16)") (class "Default")
      (node (ref "X1") (pin "16") (pinfunction "16_16") (pintype "passive"))
    )
    (net (code "150") (name "unconnected-(X1-Pad17)") (class "Default")
      (node (ref "X1") (pin "17") (pinfunction "17_17") (pintype "passive"))
    )
    (net (code "151") (name "unconnected-(X1-Pad20)") (class "Default")
      (node (ref "X1") (pin "20") (pinfunction "20_20") (pintype "passive"))
    )
    (net (code "152") (name "unconnected-(X1-Pad22)") (class "Default")
      (node (ref "X1") (pin "22") (pinfunction "22_22") (pintype "passive"))
    )
    (net (code "153") (name "unconnected-(X1-Pad23)") (class "Default")
      (node (ref "X1") (pin "23") (pinfunction "23_23") (pintype "passive"))
    )
    (net (code "154") (name "unconnected-(X1-Pad24)") (class "Default")
      (node (ref "X1") (pin "24") (pinfunction "24_24") (pintype "passive"))
    )
  )
)
